# 17-1105.net
KiCad netlist of a schematic drawn in EAGLE
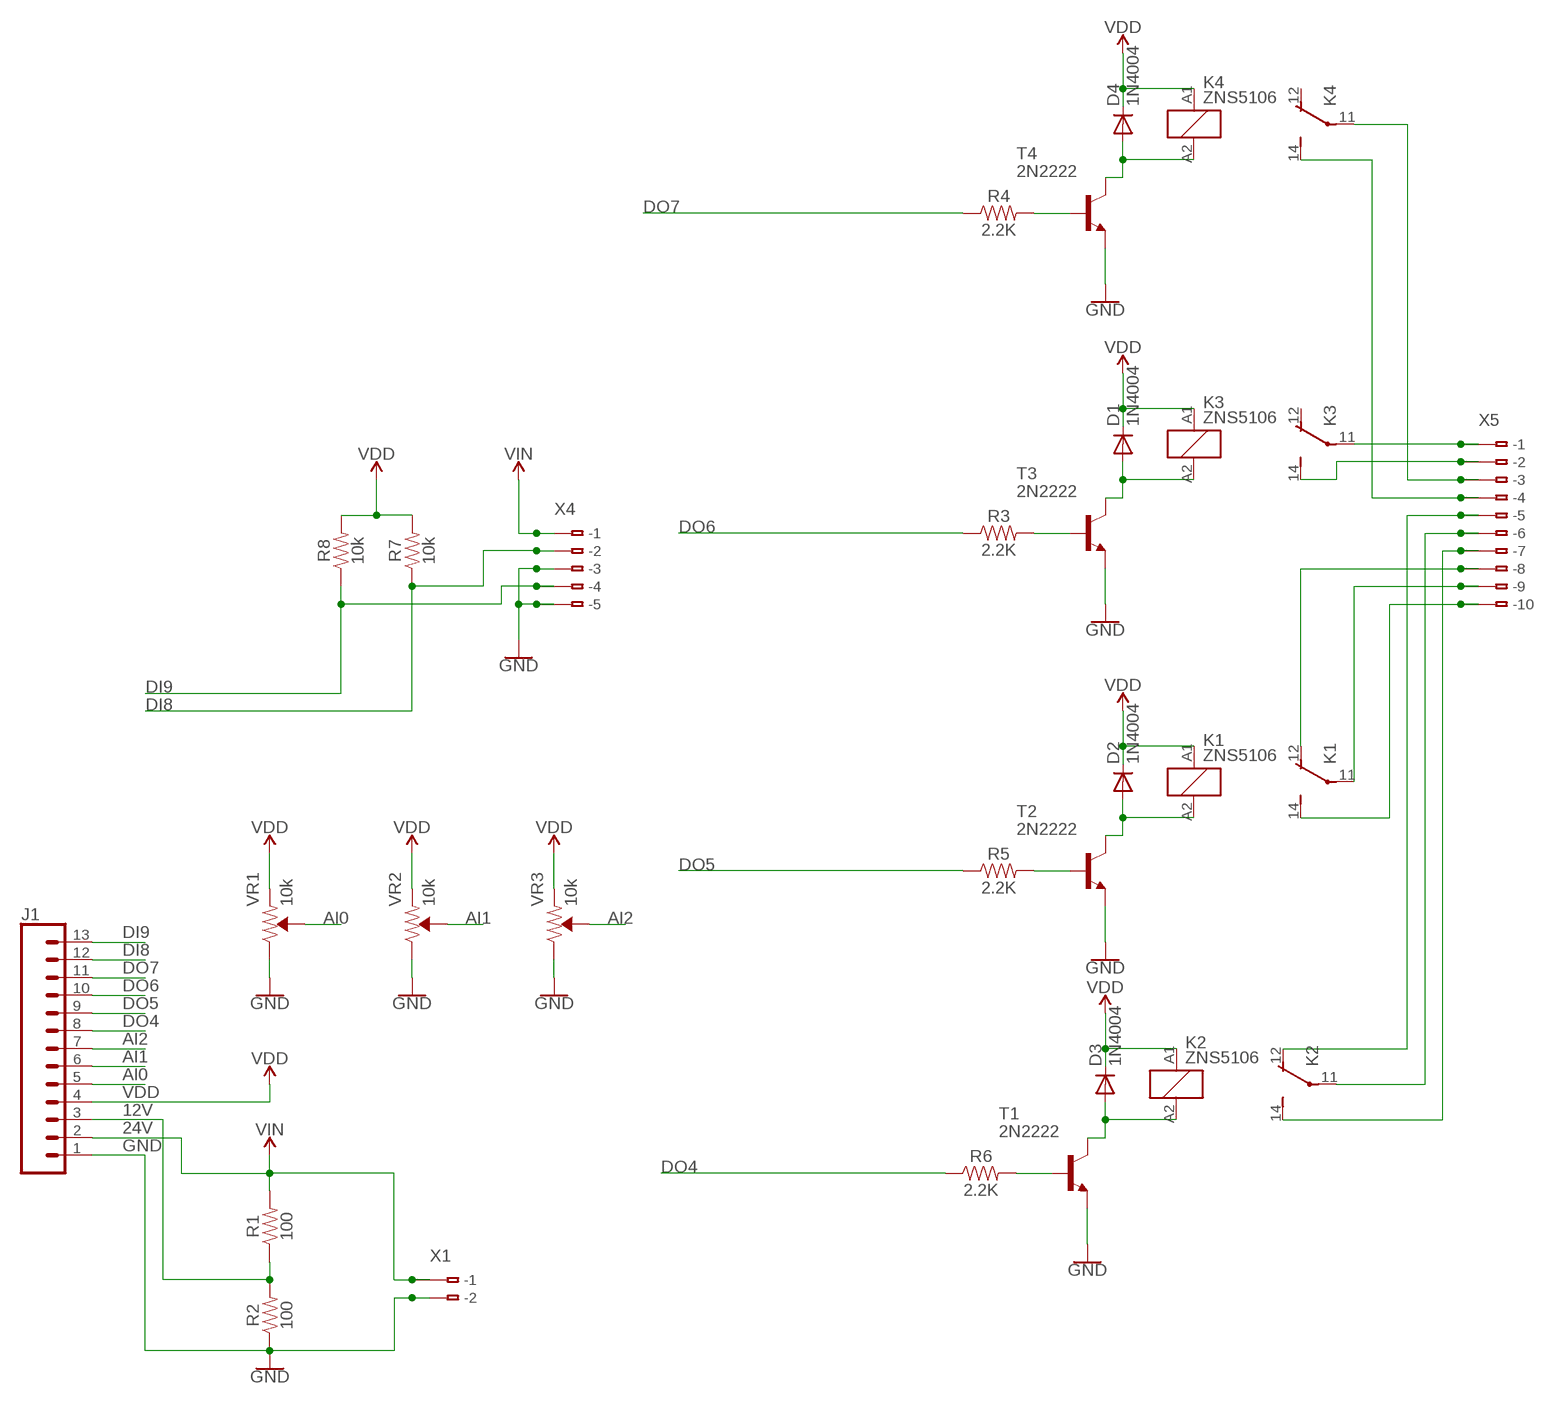
[diagram p0: schematic, sheet 1]

(export (version "E")
  (design (tool "Eeschema 10.0.6"))
  (components
    (comp (ref "D1")
      (value "1N4004")
      (footprint "eagle-import:DO41-10")
      (libsource (lib "eagle-import") (part "1N4004"))
    )
    (comp (ref "D2")
      (value "1N4004")
      (footprint "eagle-import:DO41-10")
      (libsource (lib "eagle-import") (part "1N4004"))
    )
    (comp (ref "D3")
      (value "1N4004")
      (footprint "eagle-import:DO41-10")
      (libsource (lib "eagle-import") (part "1N4004"))
    )
    (comp (ref "D4")
      (value "1N4004")
      (footprint "eagle-import:DO41-10")
      (libsource (lib "eagle-import") (part "1N4004"))
    )
    (comp (ref "J1")
      (value "CONN_13")
      (footprint "eagle-import:1X13")
      (libsource (lib "eagle-import") (part "CONN_13"))
    )
    (comp (ref "K1")
      (value "ZNS5106")
      (footprint "eagle-import:ZN5")
      (libsource (lib "eagle-import") (part "ZNS5106"))
    )
    (comp (ref "K2")
      (value "ZNS5106")
      (footprint "eagle-import:ZN5")
      (libsource (lib "eagle-import") (part "ZNS5106"))
    )
    (comp (ref "K3")
      (value "ZNS5106")
      (footprint "eagle-import:ZN5")
      (libsource (lib "eagle-import") (part "ZNS5106"))
    )
    (comp (ref "K4")
      (value "ZNS5106")
      (footprint "eagle-import:ZN5")
      (libsource (lib "eagle-import") (part "ZNS5106"))
    )
    (comp (ref "R1")
      (value "100")
      (footprint "eagle-import:AXIAL-0.3")
      (libsource (lib "eagle-import") (part "100OHM-HORIZ-1/4W-1%"))
    )
    (comp (ref "R2")
      (value "100")
      (footprint "eagle-import:AXIAL-0.3")
      (libsource (lib "eagle-import") (part "100OHM-HORIZ-1/4W-1%"))
    )
    (comp (ref "R3")
      (value "2.2K")
      (footprint "eagle-import:AXIAL-0.3")
      (libsource (lib "eagle-import") (part "RESISTORAXIAL-0.3"))
    )
    (comp (ref "R4")
      (value "2.2K")
      (footprint "eagle-import:AXIAL-0.3")
      (libsource (lib "eagle-import") (part "RESISTORAXIAL-0.3"))
    )
    (comp (ref "R5")
      (value "2.2K")
      (footprint "eagle-import:AXIAL-0.3")
      (libsource (lib "eagle-import") (part "RESISTORAXIAL-0.3"))
    )
    (comp (ref "R6")
      (value "2.2K")
      (footprint "eagle-import:AXIAL-0.3")
      (libsource (lib "eagle-import") (part "RESISTORAXIAL-0.3"))
    )
    (comp (ref "R7")
      (value "10k")
      (footprint "eagle-import:AXIAL-0.3")
      (libsource (lib "eagle-import") (part "10KOHM-HORIZ-1/4W-5%"))
    )
    (comp (ref "R8")
      (value "10k")
      (footprint "eagle-import:AXIAL-0.3")
      (libsource (lib "eagle-import") (part "10KOHM-HORIZ-1/4W-5%"))
    )
    (comp (ref "T1")
      (value "2N2222")
      (footprint "eagle-import:TO92-EBC-OVAL")
      (libsource (lib "eagle-import") (part "2N2222"))
    )
    (comp (ref "T2")
      (value "2N2222")
      (footprint "eagle-import:TO92-EBC-OVAL")
      (libsource (lib "eagle-import") (part "2N2222"))
    )
    (comp (ref "T3")
      (value "2N2222")
      (footprint "eagle-import:TO92-EBC-OVAL")
      (libsource (lib "eagle-import") (part "2N2222"))
    )
    (comp (ref "T4")
      (value "2N2222")
      (footprint "eagle-import:TO92-EBC-OVAL")
      (libsource (lib "eagle-import") (part "2N2222"))
    )
    (comp (ref "VR1")
      (value "10k")
      (footprint "eagle-import:TRIMPOT-PTH-3386U")
      (libsource (lib "eagle-import") (part "TRIMPOT-PTH-10MM-KNOB-1/2W-10%"))
    )
    (comp (ref "VR2")
      (value "10k")
      (footprint "eagle-import:TRIMPOT-PTH-3386U")
      (libsource (lib "eagle-import") (part "TRIMPOT-PTH-10MM-KNOB-1/2W-10%"))
    )
    (comp (ref "VR3")
      (value "10k")
      (footprint "eagle-import:TRIMPOT-PTH-3386U")
      (libsource (lib "eagle-import") (part "TRIMPOT-PTH-10MM-KNOB-1/2W-10%"))
    )
    (comp (ref "X1")
      (value "233-102")
      (footprint "eagle-import:233-102")
      (libsource (lib "eagle-import") (part "233-102"))
    )
    (comp (ref "X4")
      (value "233-105")
      (footprint "eagle-import:233-105")
      (libsource (lib "eagle-import") (part "233-105"))
    )
    (comp (ref "X5")
      (value "233-110")
      (footprint "eagle-import:233-110")
      (libsource (lib "eagle-import") (part "233-110"))
    )
  )
  (nets
    (net (code "1") (name "/12V") (class "Default")
      (node (ref "J1") (pin "3") (pinfunction "3_3") (pintype "passive"))
      (node (ref "R1") (pin "P$1") (pinfunction "1_P$1") (pintype "passive"))
      (node (ref "R2") (pin "P$2") (pinfunction "2_P$2") (pintype "passive"))
    )
    (net (code "2") (name "/AI0") (class "Default")
      (node (ref "J1") (pin "5") (pinfunction "5_5") (pintype "passive"))
      (node (ref "VR1") (pin "2") (pinfunction "WIPER_2") (pintype "passive"))
    )
    (net (code "3") (name "/AI1") (class "Default")
      (node (ref "J1") (pin "6") (pinfunction "6_6") (pintype "passive"))
      (node (ref "VR2") (pin "2") (pinfunction "WIPER_2") (pintype "passive"))
    )
    (net (code "4") (name "/AI2") (class "Default")
      (node (ref "J1") (pin "7") (pinfunction "7_7") (pintype "passive"))
      (node (ref "VR3") (pin "2") (pinfunction "WIPER_2") (pintype "passive"))
    )
    (net (code "5") (name "/DI8") (class "Default")
      (node (ref "J1") (pin "12") (pinfunction "12_12") (pintype "passive"))
      (node (ref "R7") (pin "P$1") (pinfunction "1_P$1") (pintype "passive"))
      (node (ref "X4") (pin "A2") (pinfunction "-2_A2") (pintype "passive"))
      (node (ref "X4") (pin "B2") (pinfunction "B-2_B2") (pintype "passive"))
    )
    (net (code "6") (name "/DI9") (class "Default")
      (node (ref "J1") (pin "13") (pinfunction "13_13") (pintype "passive"))
      (node (ref "R8") (pin "P$1") (pinfunction "1_P$1") (pintype "passive"))
      (node (ref "X4") (pin "A4") (pinfunction "-4_A4") (pintype "passive"))
      (node (ref "X4") (pin "B4") (pinfunction "B-4_B4") (pintype "passive"))
    )
    (net (code "7") (name "/DO4") (class "Default")
      (node (ref "J1") (pin "8") (pinfunction "8_8") (pintype "passive"))
      (node (ref "R6") (pin "P$1") (pinfunction "1_P$1") (pintype "passive"))
    )
    (net (code "8") (name "/DO5") (class "Default")
      (node (ref "J1") (pin "9") (pinfunction "9_9") (pintype "passive"))
      (node (ref "R5") (pin "P$1") (pinfunction "1_P$1") (pintype "passive"))
    )
    (net (code "9") (name "/DO6") (class "Default")
      (node (ref "J1") (pin "10") (pinfunction "10_10") (pintype "passive"))
      (node (ref "R3") (pin "P$1") (pinfunction "1_P$1") (pintype "passive"))
    )
    (net (code "10") (name "/DO7") (class "Default")
      (node (ref "J1") (pin "11") (pinfunction "11_11") (pintype "passive"))
      (node (ref "R4") (pin "P$1") (pinfunction "1_P$1") (pintype "passive"))
    )
    (net (code "11") (name "GND") (class "Default")
      (node (ref "J1") (pin "1") (pinfunction "1_1") (pintype "passive"))
      (node (ref "R2") (pin "P$1") (pinfunction "1_P$1") (pintype "passive"))
      (node (ref "T1") (pin "E") (pinfunction "E_E") (pintype "passive"))
      (node (ref "T2") (pin "E") (pinfunction "E_E") (pintype "passive"))
      (node (ref "T3") (pin "E") (pinfunction "E_E") (pintype "passive"))
      (node (ref "T4") (pin "E") (pinfunction "E_E") (pintype "passive"))
      (node (ref "VR1") (pin "3") (pinfunction "CW_3") (pintype "passive"))
      (node (ref "VR2") (pin "3") (pinfunction "CW_3") (pintype "passive"))
      (node (ref "VR3") (pin "3") (pinfunction "CW_3") (pintype "passive"))
      (node (ref "X1") (pin "A2") (pinfunction "-2_A2") (pintype "passive"))
      (node (ref "X1") (pin "B2") (pinfunction "B-2_B2") (pintype "passive"))
      (node (ref "X4") (pin "A3") (pinfunction "-3_A3") (pintype "passive"))
      (node (ref "X4") (pin "A5") (pinfunction "-5_A5") (pintype "passive"))
      (node (ref "X4") (pin "B3") (pinfunction "B-3_B3") (pintype "passive"))
      (node (ref "X4") (pin "B5") (pinfunction "B-5_B5") (pintype "passive"))
    )
    (net (code "12") (name "Net-(K1A-2)") (class "Default")
      (node (ref "D2") (pin "A") (pinfunction "A_A") (pintype "passive"))
      (node (ref "K1") (pin "A2") (pinfunction "2_A2") (pintype "passive"))
      (node (ref "T2") (pin "C") (pinfunction "C_C") (pintype "passive"))
    )
    (net (code "13") (name "Net-(K1B-O)") (class "Default")
      (node (ref "K1") (pin "12") (pinfunction "O_12") (pintype "passive"))
      (node (ref "X5") (pin "A8") (pinfunction "-8_A8") (pintype "passive"))
      (node (ref "X5") (pin "B8") (pinfunction "B-8_B8") (pintype "passive"))
    )
    (net (code "14") (name "Net-(K1B-P)") (class "Default")
      (node (ref "K1") (pin "11") (pinfunction "P_11") (pintype "passive"))
      (node (ref "X5") (pin "A9") (pinfunction "-9_A9") (pintype "passive"))
      (node (ref "X5") (pin "B9") (pinfunction "B-9_B9") (pintype "passive"))
    )
    (net (code "15") (name "Net-(K1B-S)") (class "Default")
      (node (ref "K1") (pin "14") (pinfunction "S_14") (pintype "passive"))
      (node (ref "X5") (pin "A10") (pinfunction "-10_A10") (pintype "passive"))
      (node (ref "X5") (pin "B10") (pinfunction "B-10_B10") (pintype "passive"))
    )
    (net (code "16") (name "Net-(K2A-2)") (class "Default")
      (node (ref "D3") (pin "A") (pinfunction "A_A") (pintype "passive"))
      (node (ref "K2") (pin "A2") (pinfunction "2_A2") (pintype "passive"))
      (node (ref "T1") (pin "C") (pinfunction "C_C") (pintype "passive"))
    )
    (net (code "17") (name "Net-(K2B-O)") (class "Default")
      (node (ref "K2") (pin "12") (pinfunction "O_12") (pintype "passive"))
      (node (ref "X5") (pin "A5") (pinfunction "-5_A5") (pintype "passive"))
      (node (ref "X5") (pin "B5") (pinfunction "B-5_B5") (pintype "passive"))
    )
    (net (code "18") (name "Net-(K2B-P)") (class "Default")
      (node (ref "K2") (pin "11") (pinfunction "P_11") (pintype "passive"))
      (node (ref "X5") (pin "A6") (pinfunction "-6_A6") (pintype "passive"))
      (node (ref "X5") (pin "B6") (pinfunction "B-6_B6") (pintype "passive"))
    )
    (net (code "19") (name "Net-(K2B-S)") (class "Default")
      (node (ref "K2") (pin "14") (pinfunction "S_14") (pintype "passive"))
      (node (ref "X5") (pin "A7") (pinfunction "-7_A7") (pintype "passive"))
      (node (ref "X5") (pin "B7") (pinfunction "B-7_B7") (pintype "passive"))
    )
    (net (code "20") (name "Net-(K3A-2)") (class "Default")
      (node (ref "D1") (pin "A") (pinfunction "A_A") (pintype "passive"))
      (node (ref "K3") (pin "A2") (pinfunction "2_A2") (pintype "passive"))
      (node (ref "T3") (pin "C") (pinfunction "C_C") (pintype "passive"))
    )
    (net (code "21") (name "Net-(K3B-P)") (class "Default")
      (node (ref "K3") (pin "11") (pinfunction "P_11") (pintype "passive"))
      (node (ref "X5") (pin "A1") (pinfunction "-1_A1") (pintype "passive"))
      (node (ref "X5") (pin "B1") (pinfunction "B-1_B1") (pintype "passive"))
    )
    (net (code "22") (name "Net-(K3B-S)") (class "Default")
      (node (ref "K3") (pin "14") (pinfunction "S_14") (pintype "passive"))
      (node (ref "X5") (pin "A2") (pinfunction "-2_A2") (pintype "passive"))
      (node (ref "X5") (pin "B2") (pinfunction "B-2_B2") (pintype "passive"))
    )
    (net (code "23") (name "Net-(K4A-2)") (class "Default")
      (node (ref "D4") (pin "A") (pinfunction "A_A") (pintype "passive"))
      (node (ref "K4") (pin "A2") (pinfunction "2_A2") (pintype "passive"))
      (node (ref "T4") (pin "C") (pinfunction "C_C") (pintype "passive"))
    )
    (net (code "24") (name "Net-(K4B-P)") (class "Default")
      (node (ref "K4") (pin "11") (pinfunction "P_11") (pintype "passive"))
      (node (ref "X5") (pin "A3") (pinfunction "-3_A3") (pintype "passive"))
      (node (ref "X5") (pin "B3") (pinfunction "B-3_B3") (pintype "passive"))
    )
    (net (code "25") (name "Net-(K4B-S)") (class "Default")
      (node (ref "K4") (pin "14") (pinfunction "S_14") (pintype "passive"))
      (node (ref "X5") (pin "A4") (pinfunction "-4_A4") (pintype "passive"))
      (node (ref "X5") (pin "B4") (pinfunction "B-4_B4") (pintype "passive"))
    )
    (net (code "26") (name "Net-(R3-2)") (class "Default")
      (node (ref "R3") (pin "P$2") (pinfunction "2_P$2") (pintype "passive"))
      (node (ref "T3") (pin "B") (pinfunction "B_B") (pintype "passive"))
    )
    (net (code "27") (name "Net-(R4-2)") (class "Default")
      (node (ref "R4") (pin "P$2") (pinfunction "2_P$2") (pintype "passive"))
      (node (ref "T4") (pin "B") (pinfunction "B_B") (pintype "passive"))
    )
    (net (code "28") (name "Net-(R5-2)") (class "Default")
      (node (ref "R5") (pin "P$2") (pinfunction "2_P$2") (pintype "passive"))
      (node (ref "T2") (pin "B") (pinfunction "B_B") (pintype "passive"))
    )
    (net (code "29") (name "Net-(R6-2)") (class "Default")
      (node (ref "R6") (pin "P$2") (pinfunction "2_P$2") (pintype "passive"))
      (node (ref "T1") (pin "B") (pinfunction "B_B") (pintype "passive"))
    )
    (net (code "30") (name "VDD") (class "Default")
      (node (ref "D1") (pin "C") (pinfunction "C_C") (pintype "passive"))
      (node (ref "D2") (pin "C") (pinfunction "C_C") (pintype "passive"))
      (node (ref "D3") (pin "C") (pinfunction "C_C") (pintype "passive"))
      (node (ref "D4") (pin "C") (pinfunction "C_C") (pintype "passive"))
      (node (ref "J1") (pin "4") (pinfunction "4_4") (pintype "passive"))
      (node (ref "K1") (pin "A1") (pinfunction "1_A1") (pintype "passive"))
      (node (ref "K2") (pin "A1") (pinfunction "1_A1") (pintype "passive"))
      (node (ref "K3") (pin "A1") (pinfunction "1_A1") (pintype "passive"))
      (node (ref "K4") (pin "A1") (pinfunction "1_A1") (pintype "passive"))
      (node (ref "R7") (pin "P$2") (pinfunction "2_P$2") (pintype "passive"))
      (node (ref "R8") (pin "P$2") (pinfunction "2_P$2") (pintype "passive"))
      (node (ref "VR1") (pin "1") (pinfunction "CCW_1") (pintype "passive"))
      (node (ref "VR2") (pin "1") (pinfunction "CCW_1") (pintype "passive"))
      (node (ref "VR3") (pin "1") (pinfunction "CCW_1") (pintype "passive"))
    )
    (net (code "31") (name "VIN") (class "Default")
      (node (ref "J1") (pin "2") (pinfunction "2_2") (pintype "passive"))
      (node (ref "R1") (pin "P$2") (pinfunction "2_P$2") (pintype "passive"))
      (node (ref "X1") (pin "A1") (pinfunction "-1_A1") (pintype "passive"))
      (node (ref "X1") (pin "B1") (pinfunction "B-1_B1") (pintype "passive"))
      (node (ref "X4") (pin "A1") (pinfunction "-1_A1") (pintype "passive"))
      (node (ref "X4") (pin "B1") (pinfunction "B-1_B1") (pintype "passive"))
    )
    (net (code "32") (name "unconnected-(K3B-O-Pad12)") (class "Default")
      (node (ref "K3") (pin "12") (pinfunction "O_12") (pintype "passive"))
    )
    (net (code "33") (name "unconnected-(K4B-O-Pad12)") (class "Default")
      (node (ref "K4") (pin "12") (pinfunction "O_12") (pintype "passive"))
    )
  )
)
